# IndicatorControl.net
KiCad netlist of a schematic drawn in Altium Designer
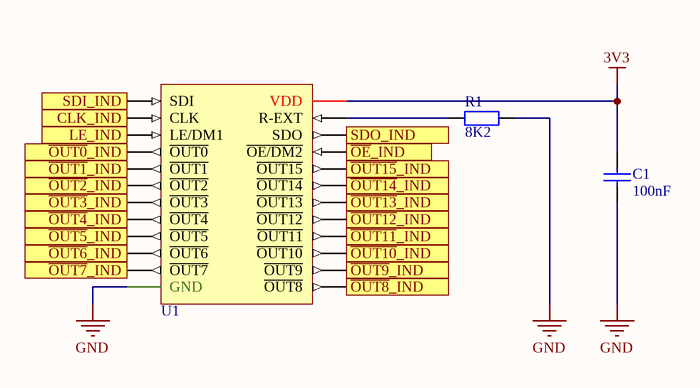
[diagram p0: IndicatorControl.SchDoc]

(export (version "E")
  (design (tool "Eeschema 10.0.6"))
  (components
    (comp (ref "C1")
      (value "100nF")
      (footprint "FP_0805_CAP_085")
      (description "Capacitor")
      (fields (field (name "TOLERANCE") "+80%/-20%") (field (name "VOLTAGE") "25V"))
      (libsource (lib "hallglib") (part "CAP 100nF"))
    )
    (comp (ref "R1")
      (value "8K2")
      (footprint "FP_0805_RES")
      (description "Resistor")
      (fields (field (name "TOLERANCE") "5%") (field (name "POWER") "125mW"))
      (libsource (lib "hallglib") (part "RES 8K2"))
    )
    (comp (ref "U1")
      (value "STP16CP05TTR")
      (footprint "24-Pin TSSOP")
      (description "Led Driver, 16 Outputs, Constant Current, 3V-5.5V in, 30MHz switch, 20V/100mA out, TSSOP-24")
      (libsource (lib "RobonAUT") (part "STP16CP05TTR"))
    )
  )
  (nets
    (net (code "1") (name "/CLK_IND") (class "Default")
      (node (ref "U1") (pin "3") (pinfunction "CLK_3") (pintype "input"))
    )
    (net (code "2") (name "/LE_IND") (class "Default")
      (node (ref "U1") (pin "4") (pinfunction "LE/DM1_4") (pintype "input"))
    )
    (net (code "3") (name "/SDI_IND") (class "Default")
      (node (ref "U1") (pin "2") (pinfunction "SDI_2") (pintype "input"))
    )
    (net (code "4") (name "/SDO_IND") (class "Default")
      (node (ref "U1") (pin "22") (pinfunction "SDO_22") (pintype "output"))
    )
    (net (code "5") (name "/~{OE}_IND") (class "Default")
      (node (ref "U1") (pin "21") (pinfunction "~{OE/DM2}_21") (pintype "input"))
    )
    (net (code "6") (name "/~{OUT0}_IND") (class "Default")
      (node (ref "U1") (pin "5") (pinfunction "~{OUT0}_5") (pintype "output"))
    )
    (net (code "7") (name "/~{OUT1}_IND") (class "Default")
      (node (ref "U1") (pin "6") (pinfunction "~{OUT1}_6") (pintype "output"))
    )
    (net (code "8") (name "/~{OUT2}_IND") (class "Default")
      (node (ref "U1") (pin "7") (pinfunction "~{OUT2}_7") (pintype "output"))
    )
    (net (code "9") (name "/~{OUT3}_IND") (class "Default")
      (node (ref "U1") (pin "8") (pinfunction "~{OUT3}_8") (pintype "output"))
    )
    (net (code "10") (name "/~{OUT4}_IND") (class "Default")
      (node (ref "U1") (pin "9") (pinfunction "~{OUT4}_9") (pintype "output"))
    )
    (net (code "11") (name "/~{OUT5}_IND") (class "Default")
      (node (ref "U1") (pin "10") (pinfunction "~{OUT5}_10") (pintype "output"))
    )
    (net (code "12") (name "/~{OUT6}_IND") (class "Default")
      (node (ref "U1") (pin "11") (pinfunction "~{OUT6}_11") (pintype "output"))
    )
    (net (code "13") (name "/~{OUT7}_IND") (class "Default")
      (node (ref "U1") (pin "12") (pinfunction "~{OUT7}_12") (pintype "output"))
    )
    (net (code "14") (name "/~{OUT8}_IND") (class "Default")
      (node (ref "U1") (pin "13") (pinfunction "~{OUT8}_13") (pintype "output"))
    )
    (net (code "15") (name "/~{OUT9}_IND") (class "Default")
      (node (ref "U1") (pin "14") (pinfunction "~{OUT9}_14") (pintype "output"))
    )
    (net (code "16") (name "/~{OUT10}_IND") (class "Default")
      (node (ref "U1") (pin "15") (pinfunction "~{OUT10}_15") (pintype "output"))
    )
    (net (code "17") (name "/~{OUT11}_IND") (class "Default")
      (node (ref "U1") (pin "16") (pinfunction "~{OUT11}_16") (pintype "output"))
    )
    (net (code "18") (name "/~{OUT12}_IND") (class "Default")
      (node (ref "U1") (pin "17") (pinfunction "~{OUT12}_17") (pintype "output"))
    )
    (net (code "19") (name "/~{OUT13}_IND") (class "Default")
      (node (ref "U1") (pin "18") (pinfunction "~{OUT13}_18") (pintype "output"))
    )
    (net (code "20") (name "/~{OUT14}_IND") (class "Default")
      (node (ref "U1") (pin "19") (pinfunction "~{OUT14}_19") (pintype "output"))
    )
    (net (code "21") (name "/~{OUT15}_IND") (class "Default")
      (node (ref "U1") (pin "20") (pinfunction "~{OUT15}_20") (pintype "output"))
    )
    (net (code "22") (name "3V3") (class "Default")
      (node (ref "C1") (pin "2") (pinfunction "2_2") (pintype "passive"))
      (node (ref "U1") (pin "24") (pinfunction "VDD_24") (pintype "power_in"))
    )
    (net (code "23") (name "GND") (class "Default")
      (node (ref "C1") (pin "1") (pinfunction "1_1") (pintype "passive"))
      (node (ref "R1") (pin "2") (pinfunction "2_2") (pintype "passive"))
      (node (ref "U1") (pin "1") (pinfunction "GND_1") (pintype "power_in"))
    )
    (net (code "24") (name "Net-(U1-R-EXT)") (class "Default")
      (node (ref "R1") (pin "1") (pinfunction "1_1") (pintype "passive"))
      (node (ref "U1") (pin "23") (pinfunction "R-EXT_23") (pintype "input"))
    )
  )
)
